# S2C_IOsVIO.net
KiCad netlist of a schematic drawn in Altium Designer
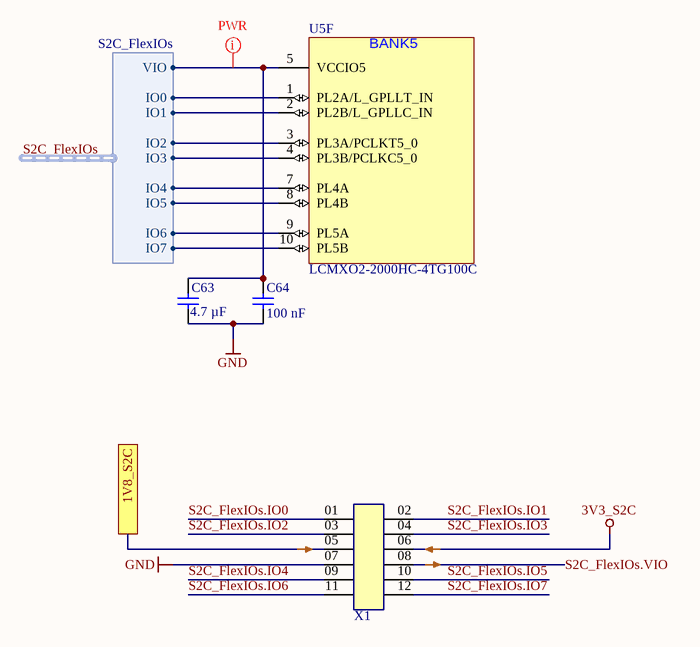
[diagram p0: S2C_IOsVIO.SchDoc]

(export (version "E")
  (design (tool "Eeschema 10.0.6"))
  (components
    (comp (ref "C63")
      (value "4.7 µF")
      (footprint "C_0603_TE")
      (description "Generic capacitor")
      (fields
        (field (name "MANUFACTURER PART NUMBER") "UZgen_C_0603_4.7uF_16V_X5R")
        (field (name "MANUFACTURER") "UZgen")
        (field (name "CREATED FROM") "MGeier")
      )
      (libsource (lib "user") (part "CAP-NP"))
    )
    (comp (ref "C64")
      (value "100 nF")
      (footprint "C_0603_TE")
      (description "Generic capacitor")
      (fields
        (field (name "TOLERANCE") "10 %")
        (field (name "VOLTAGE") "50 V")
        (field (name "CREATED FROM") "AGeiger")
      )
      (libsource (lib "user") (part "CAP-NP"))
    )
    (comp (ref "U5")
      (value "LCMXO2-2000HC-4TG100C")
      (footprint "QFP50P1600X1600X160-100N")
      (description "TQFP-100(14x14) Programmable Logic Device (CPLDs/FPGAs) ROHS")
      (fields
        (field (name "MANUFACTURER") "Lattice")
        (field (name "LCSC PART NUMBER") "C1521632")
        (field (name "CREATED FROM") "FRosner")
      )
      (libsource (lib "user") (part "LCMXO2-2000"))
    )
    (comp (ref "X1")
      (value "PH 0.1\" SMD 2x06")
      (footprint "TSM-106-01-L-DV")
      (description "0.1\" Double-row Pin Header, 90°-to-PCB SMD, 2x06 Pins, 250V, 3A")
      (fields
        (field (name "MANUFACTURER PART NUMBER") "UZgen_Conn_PinHead_2x06_SMD_100mil_90deg")
        (field (name "MANUFACTURER") "UZgen")
        (field (name "CREATED FROM") "UZgenTool")
      )
      (libsource (lib "user") (part "PinHeader_2x06"))
    )
  )
  (nets
    (net (code "2") (name "/1V8_S2C") (class "Default")
      (node (ref "X1") (pin "05") (pinfunction "05_05") (pintype "passive"))
    )
    (net (code "3") (name "/IO0") (class "Default")
      (node (ref "U5") (pin "1") (pinfunction "PL2A/L_GPLLT_IN_1") (pintype "bidirectional"))
    )
    (net (code "4") (name "/IO1") (class "Default")
      (node (ref "U5") (pin "2") (pinfunction "PL2B/L_GPLLC_IN_2") (pintype "bidirectional"))
    )
    (net (code "5") (name "/IO2") (class "Default")
      (node (ref "U5") (pin "3") (pinfunction "PL3A/PCLKT5_0_3") (pintype "bidirectional"))
    )
    (net (code "6") (name "/IO3") (class "Default")
      (node (ref "U5") (pin "4") (pinfunction "PL3B/PCLKC5_0_4") (pintype "bidirectional"))
    )
    (net (code "7") (name "/IO4") (class "Default")
      (node (ref "U5") (pin "7") (pinfunction "PL4A_7") (pintype "bidirectional"))
    )
    (net (code "8") (name "/IO5") (class "Default")
      (node (ref "U5") (pin "8") (pinfunction "PL4B_8") (pintype "bidirectional"))
    )
    (net (code "9") (name "/IO6") (class "Default")
      (node (ref "U5") (pin "9") (pinfunction "PL5A_9") (pintype "bidirectional"))
    )
    (net (code "10") (name "/IO7") (class "Default")
      (node (ref "U5") (pin "10") (pinfunction "PL5B_10") (pintype "bidirectional"))
    )
    (net (code "11") (name "/S2C_FlexIOs.IO0") (class "Default")
      (node (ref "X1") (pin "01") (pinfunction "01_01") (pintype "passive"))
    )
    (net (code "12") (name "/S2C_FlexIOs.IO1") (class "Default")
      (node (ref "X1") (pin "02") (pinfunction "02_02") (pintype "passive"))
    )
    (net (code "13") (name "/S2C_FlexIOs.IO2") (class "Default")
      (node (ref "X1") (pin "03") (pinfunction "03_03") (pintype "passive"))
    )
    (net (code "14") (name "/S2C_FlexIOs.IO3") (class "Default")
      (node (ref "X1") (pin "04") (pinfunction "04_04") (pintype "passive"))
    )
    (net (code "15") (name "/S2C_FlexIOs.IO4") (class "Default")
      (node (ref "X1") (pin "09") (pinfunction "09_09") (pintype "passive"))
    )
    (net (code "16") (name "/S2C_FlexIOs.IO5") (class "Default")
      (node (ref "X1") (pin "10") (pinfunction "10_10") (pintype "passive"))
    )
    (net (code "17") (name "/S2C_FlexIOs.IO6") (class "Default")
      (node (ref "X1") (pin "11") (pinfunction "11_11") (pintype "passive"))
    )
    (net (code "18") (name "/S2C_FlexIOs.IO7") (class "Default")
      (node (ref "X1") (pin "12") (pinfunction "12_12") (pintype "passive"))
    )
    (net (code "19") (name "/S2C_FlexIOs.VIO") (class "Default")
      (node (ref "X1") (pin "08") (pinfunction "08_08") (pintype "passive"))
    )
    (net (code "21") (name "/VIO") (class "Default")
      (node (ref "C63") (pin "1") (pinfunction "1_1") (pintype "passive"))
      (node (ref "C64") (pin "2") (pinfunction "2_2") (pintype "passive"))
      (node (ref "U5") (pin "5") (pinfunction "VCCIO5_5") (pintype "power_in"))
    )
    (net (code "22") (name "3V3_S2C") (class "Default")
      (node (ref "X1") (pin "06") (pinfunction "06_06") (pintype "passive"))
    )
    (net (code "23") (name "GND") (class "Default")
      (node (ref "C63") (pin "2") (pinfunction "2_2") (pintype "passive"))
      (node (ref "C64") (pin "1") (pinfunction "1_1") (pintype "passive"))
      (node (ref "X1") (pin "07") (pinfunction "07_07") (pintype "passive"))
    )
  )
)
